# MCU_DBG.net
KiCad netlist of a schematic drawn in Altium Designer
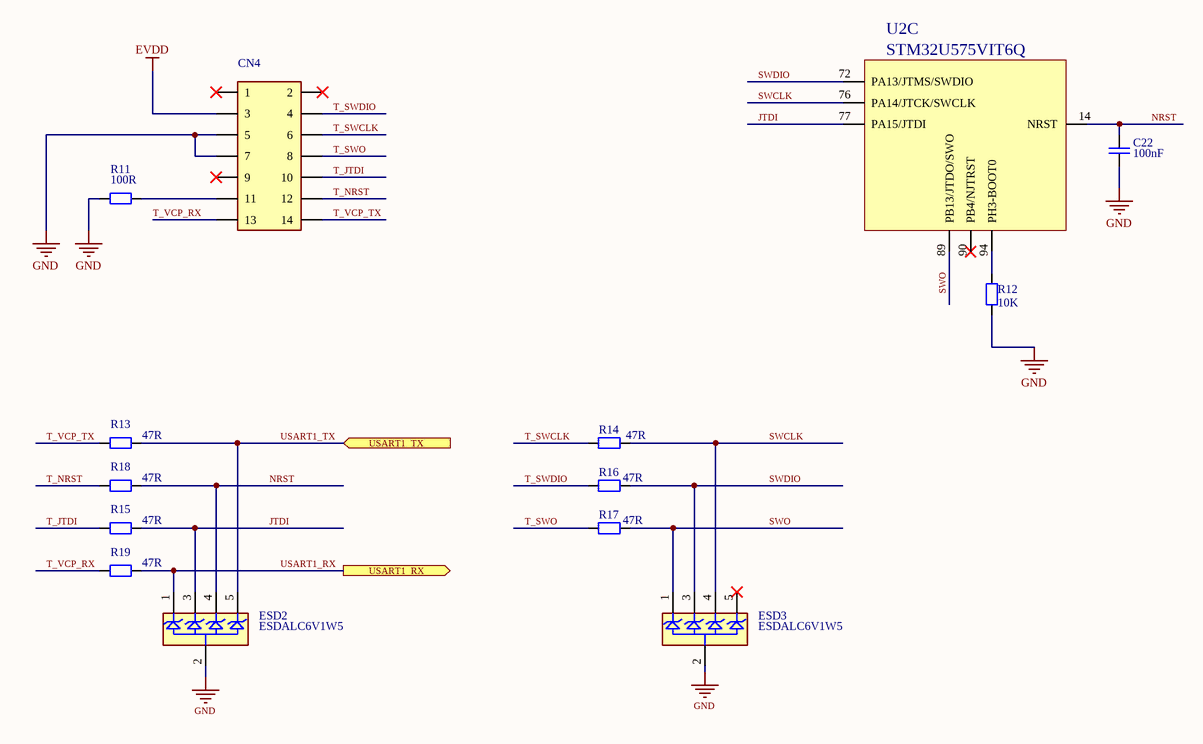
[diagram p0: MCU_DBG.SchDoc]

(export (version "E")
  (design (tool "Eeschema 10.0.6"))
  (components
    (comp (ref "C22")
      (value "100nF")
      (footprint "CAP_SM0805_YAGEOCC2_N")
      (description "CAP 100nF SM0805 X7R 50V YAGEO CC2")
      (fields
        (field (name "MANUFACTURER") "Yageo")
        (field (name "MANUFACTURER PART NUMBER") "CC0805KRX7R9BB104")
      )
      (libsource (lib "Yageo") (part "CC0805KRX7R9BB104"))
    )
    (comp (ref "CN4")
      (value "20021511-00014T4LF")
      (footprint "2002151100014T4LF")
      (description "1.27mm (0.05in.) pitch, Shrouded header, 14 contacts")
      (fields (field (name "MANUFACTURER") "Amphenol ICC"))
      (libsource (lib "header_shrouded") (part "20021511-00014T4LF"))
    )
    (comp (ref "ESD2")
      (value "ESDALC6V1W5")
      (footprint "ESDALC6V1W5")
      (fields (field (name "MANUFACTURER") "ST"))
      (libsource (lib "diode") (part "ESDALC6V1W5"))
    )
    (comp (ref "ESD3")
      (value "ESDALC6V1W5")
      (footprint "ESDALC6V1W5")
      (fields (field (name "MANUFACTURER") "ST"))
      (libsource (lib "diode") (part "ESDALC6V1W5"))
    )
    (comp (ref "R11")
      (value "100R")
      (footprint "RES_SM0805_YAGEORC_N")
      (description "RES 100R SM0805 YAGEO RC_L")
      (fields
        (field (name "MANUFACTURER") "Yageo")
        (field (name "MANUFACTURER PART NUMBER") "RC0805FR-07100RL")
      )
      (libsource (lib "Yageo") (part "RC0805FR-07100RL"))
    )
    (comp (ref "R12")
      (value "10K")
      (footprint "RES_SM0805_YAGEORC_N")
      (description "RES 10K SM0805 YAGEO RC_L")
      (fields
        (field (name "MANUFACTURER") "Yageo")
        (field (name "MANUFACTURER PART NUMBER") "RC0805FR-0710KL")
      )
      (libsource (lib "Yageo") (part "RC0805FR-0710KL"))
    )
    (comp (ref "R13")
      (value "47R")
      (footprint "RES_SM0805_YAGEORC_N")
      (description "RES 47R SM0805 YAGEO RC_L")
      (fields
        (field (name "MANUFACTURER") "Yageo")
        (field (name "MANUFACTURER PART NUMBER") "RC0805FR-0747RL")
      )
      (libsource (lib "Yageo") (part "RC0805FR-0747RL"))
    )
    (comp (ref "R14")
      (value "47R")
      (footprint "RES_SM0805_YAGEORC_N")
      (description "RES 47R SM0805 YAGEO RC_L")
      (fields
        (field (name "MANUFACTURER") "Yageo")
        (field (name "MANUFACTURER PART NUMBER") "RC0805FR-0747RL")
      )
      (libsource (lib "Yageo") (part "RC0805FR-0747RL"))
    )
    (comp (ref "R15")
      (value "47R")
      (footprint "RES_SM0805_YAGEORC_N")
      (description "RES 47R SM0805 YAGEO RC_L")
      (fields
        (field (name "MANUFACTURER") "Yageo")
        (field (name "MANUFACTURER PART NUMBER") "RC0805FR-0747RL")
      )
      (libsource (lib "Yageo") (part "RC0805FR-0747RL"))
    )
    (comp (ref "R16")
      (value "47R")
      (footprint "RES_SM0805_YAGEORC_N")
      (description "RES 47R SM0805 YAGEO RC_L")
      (fields
        (field (name "MANUFACTURER") "Yageo")
        (field (name "MANUFACTURER PART NUMBER") "RC0805FR-0747RL")
      )
      (libsource (lib "Yageo") (part "RC0805FR-0747RL"))
    )
    (comp (ref "R17")
      (value "47R")
      (footprint "RES_SM0805_YAGEORC_N")
      (description "RES 47R SM0805 YAGEO RC_L")
      (fields
        (field (name "MANUFACTURER") "Yageo")
        (field (name "MANUFACTURER PART NUMBER") "RC0805FR-0747RL")
      )
      (libsource (lib "Yageo") (part "RC0805FR-0747RL"))
    )
    (comp (ref "R18")
      (value "47R")
      (footprint "RES_SM0805_YAGEORC_N")
      (description "RES 47R SM0805 YAGEO RC_L")
      (fields
        (field (name "MANUFACTURER") "Yageo")
        (field (name "MANUFACTURER PART NUMBER") "RC0805FR-0747RL")
      )
      (libsource (lib "Yageo") (part "RC0805FR-0747RL"))
    )
    (comp (ref "R19")
      (value "47R")
      (footprint "RES_SM0805_YAGEORC_N")
      (description "RES 47R SM0805 YAGEO RC_L")
      (fields
        (field (name "MANUFACTURER") "Yageo")
        (field (name "MANUFACTURER PART NUMBER") "RC0805FR-0747RL")
      )
      (libsource (lib "Yageo") (part "RC0805FR-0747RL"))
    )
    (comp (ref "U2")
      (value "STM32U575VIT6Q")
      (footprint "STM32U575VI")
      (fields (field (name "MANUFACTURER") "ST"))
      (libsource (lib "Microcontroladores") (part "STM32U575VI_1"))
    )
  )
  (nets
    (net (code "1") (name "/JTDI") (class "Default")
      (node (ref "ESD2") (pin "3") (pinfunction "I/02_3") (pintype "passive"))
      (node (ref "R15") (pin "2") (pintype "passive"))
      (node (ref "U2") (pin "77") (pinfunction "PA15/JTDI_77") (pintype "passive"))
    )
    (net (code "2") (name "/NRST") (class "Default")
      (node (ref "C22") (pin "1") (pintype "passive"))
      (node (ref "ESD2") (pin "4") (pinfunction "I/03_4") (pintype "passive"))
      (node (ref "R18") (pin "2") (pintype "passive"))
      (node (ref "U2") (pin "14") (pinfunction "NRST_14") (pintype "passive"))
    )
    (net (code "3") (name "/SWCLK") (class "Default")
      (node (ref "ESD3") (pin "4") (pinfunction "I/03_4") (pintype "passive"))
      (node (ref "R14") (pin "2") (pintype "passive"))
      (node (ref "U2") (pin "76") (pinfunction "PA14/JTCK/SWCLK_76") (pintype "passive"))
    )
    (net (code "4") (name "/SWDIO") (class "Default")
      (node (ref "ESD3") (pin "3") (pinfunction "I/02_3") (pintype "passive"))
      (node (ref "R16") (pin "2") (pintype "passive"))
      (node (ref "U2") (pin "72") (pinfunction "PA13/JTMS/SWDIO_72") (pintype "passive"))
    )
    (net (code "5") (name "/SWO") (class "Default")
      (node (ref "ESD3") (pin "1") (pinfunction "I/01_1") (pintype "passive"))
      (node (ref "R17") (pin "2") (pintype "passive"))
      (node (ref "U2") (pin "89") (pinfunction "PB13/JTDO/SWO_89") (pintype "passive"))
    )
    (net (code "6") (name "/T_JTDI") (class "Default")
      (node (ref "CN4") (pin "10") (pinfunction "10_10") (pintype "passive"))
      (node (ref "R15") (pin "1") (pintype "passive"))
    )
    (net (code "7") (name "/T_NRST") (class "Default")
      (node (ref "CN4") (pin "12") (pinfunction "12_12") (pintype "passive"))
      (node (ref "R18") (pin "1") (pintype "passive"))
    )
    (net (code "8") (name "/T_SWCLK") (class "Default")
      (node (ref "CN4") (pin "6") (pinfunction "6_6") (pintype "passive"))
      (node (ref "R14") (pin "1") (pintype "passive"))
    )
    (net (code "9") (name "/T_SWDIO") (class "Default")
      (node (ref "CN4") (pin "4") (pinfunction "4_4") (pintype "passive"))
      (node (ref "R16") (pin "1") (pintype "passive"))
    )
    (net (code "10") (name "/T_SWO") (class "Default")
      (node (ref "CN4") (pin "8") (pinfunction "8_8") (pintype "passive"))
      (node (ref "R17") (pin "1") (pintype "passive"))
    )
    (net (code "11") (name "/T_VCP_RX") (class "Default")
      (node (ref "CN4") (pin "13") (pinfunction "13_13") (pintype "passive"))
      (node (ref "R19") (pin "1") (pintype "passive"))
    )
    (net (code "12") (name "/T_VCP_TX") (class "Default")
      (node (ref "CN4") (pin "14") (pinfunction "14_14") (pintype "passive"))
      (node (ref "R13") (pin "1") (pintype "passive"))
    )
    (net (code "13") (name "/USART1_RX") (class "Default")
      (node (ref "ESD2") (pin "1") (pinfunction "I/01_1") (pintype "passive"))
      (node (ref "R19") (pin "2") (pintype "passive"))
    )
    (net (code "14") (name "/USART1_TX") (class "Default")
      (node (ref "ESD2") (pin "5") (pinfunction "I/04_5") (pintype "passive"))
      (node (ref "R13") (pin "2") (pintype "passive"))
    )
    (net (code "15") (name "EVDD") (class "Default")
      (node (ref "CN4") (pin "3") (pinfunction "3_3") (pintype "passive"))
    )
    (net (code "16") (name "GND") (class "Default")
      (node (ref "C22") (pin "2") (pintype "passive"))
      (node (ref "CN4") (pin "5") (pinfunction "5_5") (pintype "passive"))
      (node (ref "CN4") (pin "7") (pinfunction "7_7") (pintype "passive"))
      (node (ref "ESD2") (pin "2") (pinfunction "GND_2") (pintype "passive"))
      (node (ref "ESD3") (pin "2") (pinfunction "GND_2") (pintype "passive"))
      (node (ref "R11") (pin "1") (pintype "passive"))
      (node (ref "R12") (pin "1") (pintype "passive"))
    )
    (net (code "17") (name "Net-(CN4-Pad11)") (class "Default")
      (node (ref "CN4") (pin "11") (pinfunction "11_11") (pintype "passive"))
      (node (ref "R11") (pin "2") (pintype "passive"))
    )
    (net (code "18") (name "Net-(U2C-PH3-BOOT0)") (class "Default")
      (node (ref "R12") (pin "2") (pintype "passive"))
      (node (ref "U2") (pin "94") (pinfunction "PH3-BOOT0_94") (pintype "passive"))
    )
    (net (code "19") (name "unconnected-(CN4-Pad1)") (class "Default")
      (node (ref "CN4") (pin "1") (pinfunction "1_1") (pintype "passive+no_connect"))
    )
    (net (code "20") (name "unconnected-(CN4-Pad2)") (class "Default")
      (node (ref "CN4") (pin "2") (pinfunction "2_2") (pintype "passive+no_connect"))
    )
    (net (code "21") (name "unconnected-(CN4-Pad9)") (class "Default")
      (node (ref "CN4") (pin "9") (pinfunction "9_9") (pintype "passive+no_connect"))
    )
    (net (code "22") (name "unconnected-(ESD3-I{slash}04-Pad5)") (class "Default")
      (node (ref "ESD3") (pin "5") (pinfunction "I/04_5") (pintype "passive+no_connect"))
    )
    (net (code "23") (name "unconnected-(U2C-PB4{slash}NJTRST-Pad90)") (class "Default")
      (node (ref "U2") (pin "90") (pinfunction "PB4/NJTRST_90") (pintype "passive+no_connect"))
    )
  )
)
